# display.net
KiCad netlist of a schematic drawn in EAGLE
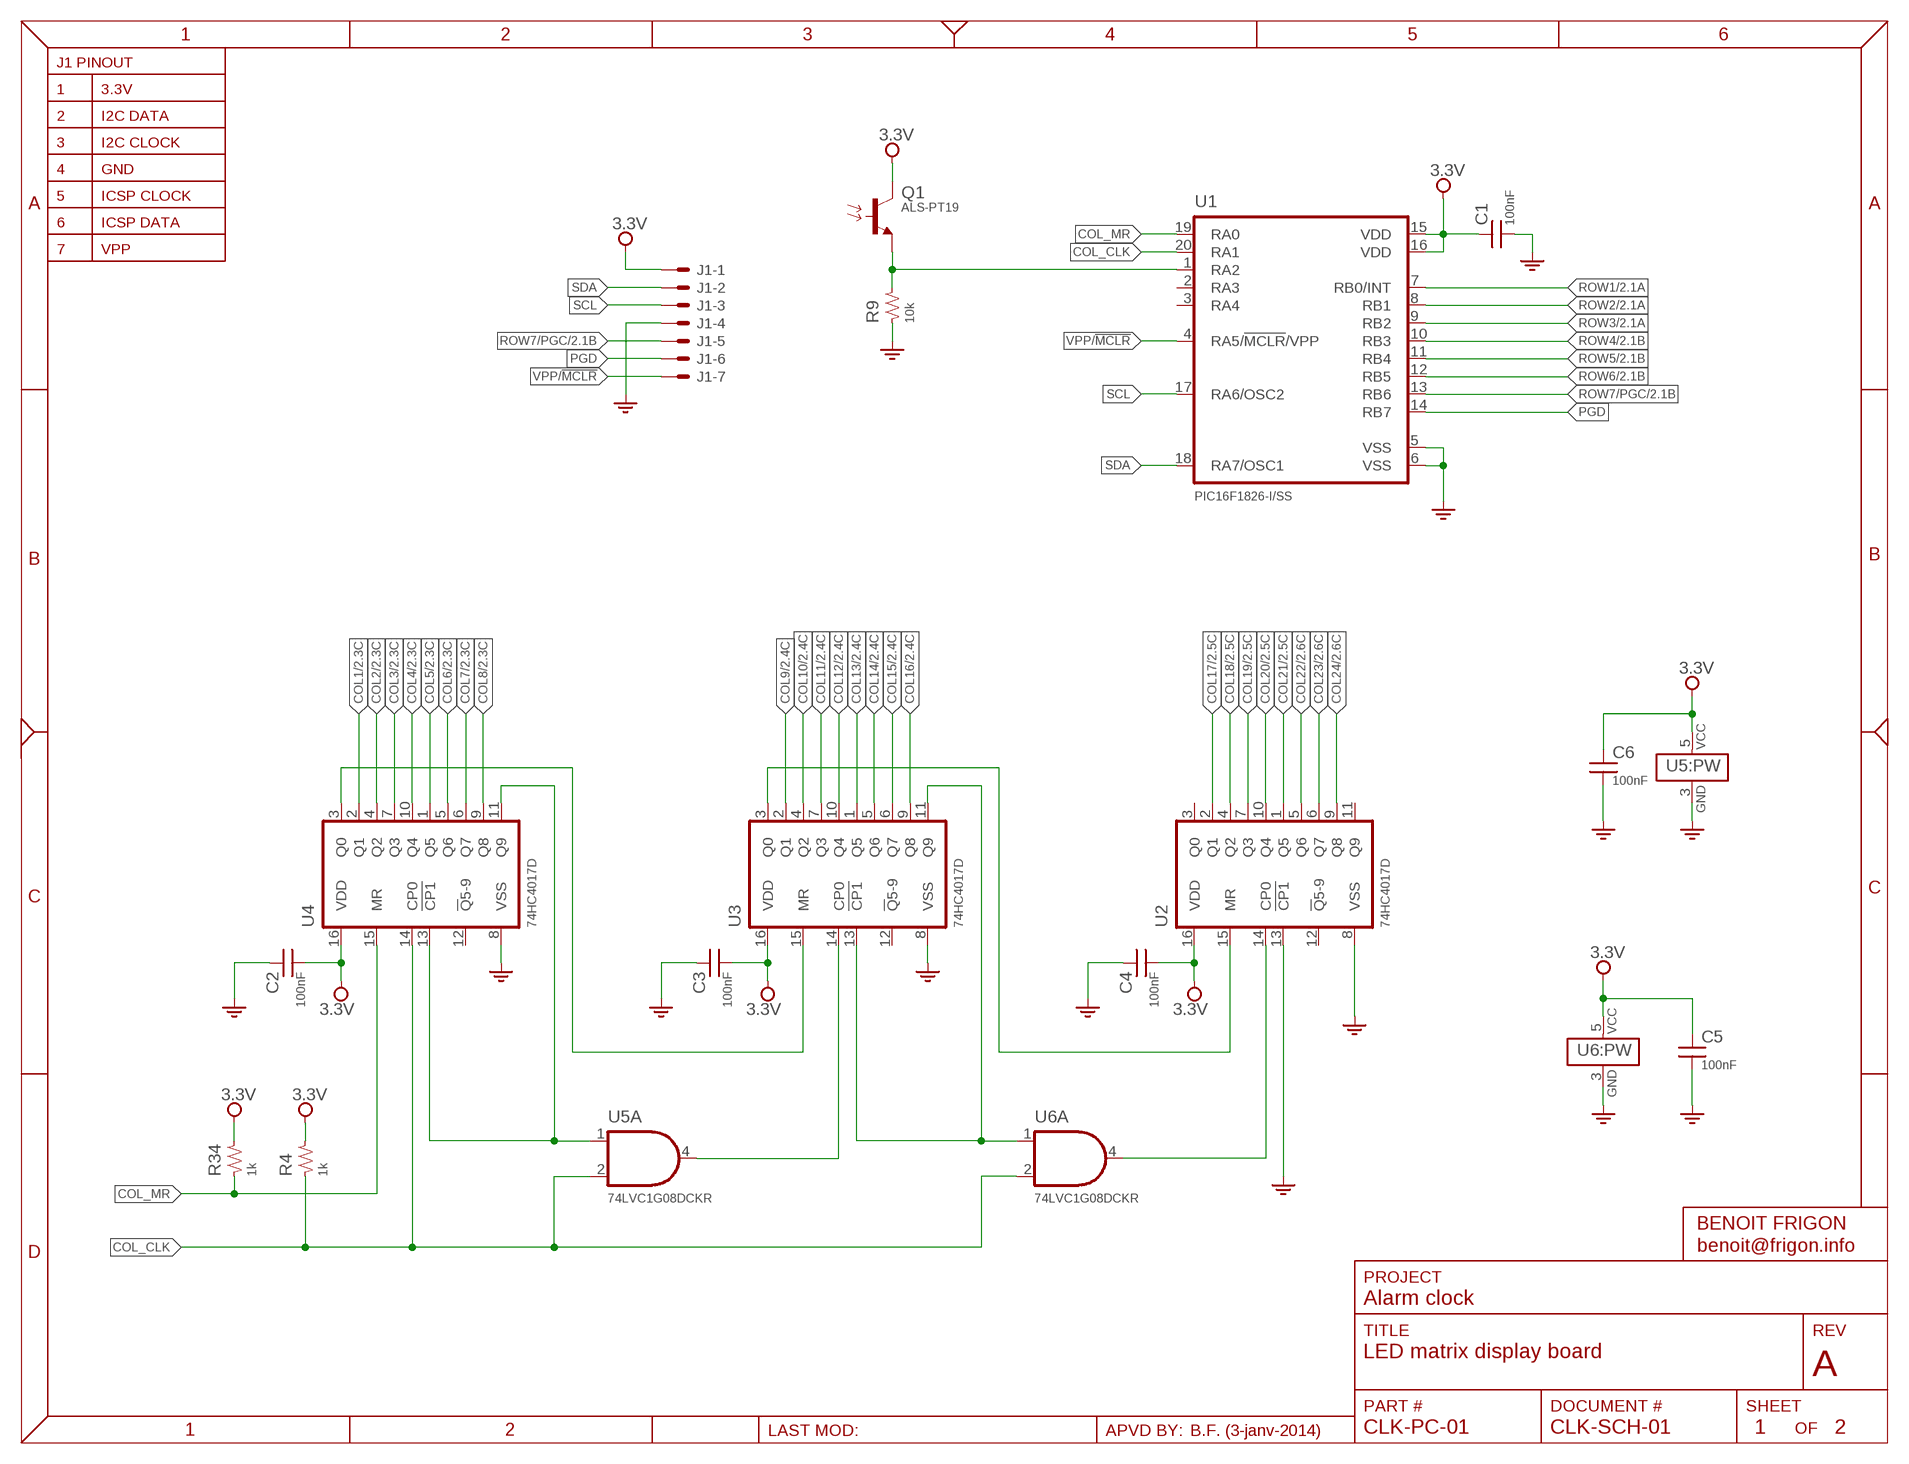
[diagram p0: schematic, sheet 1]
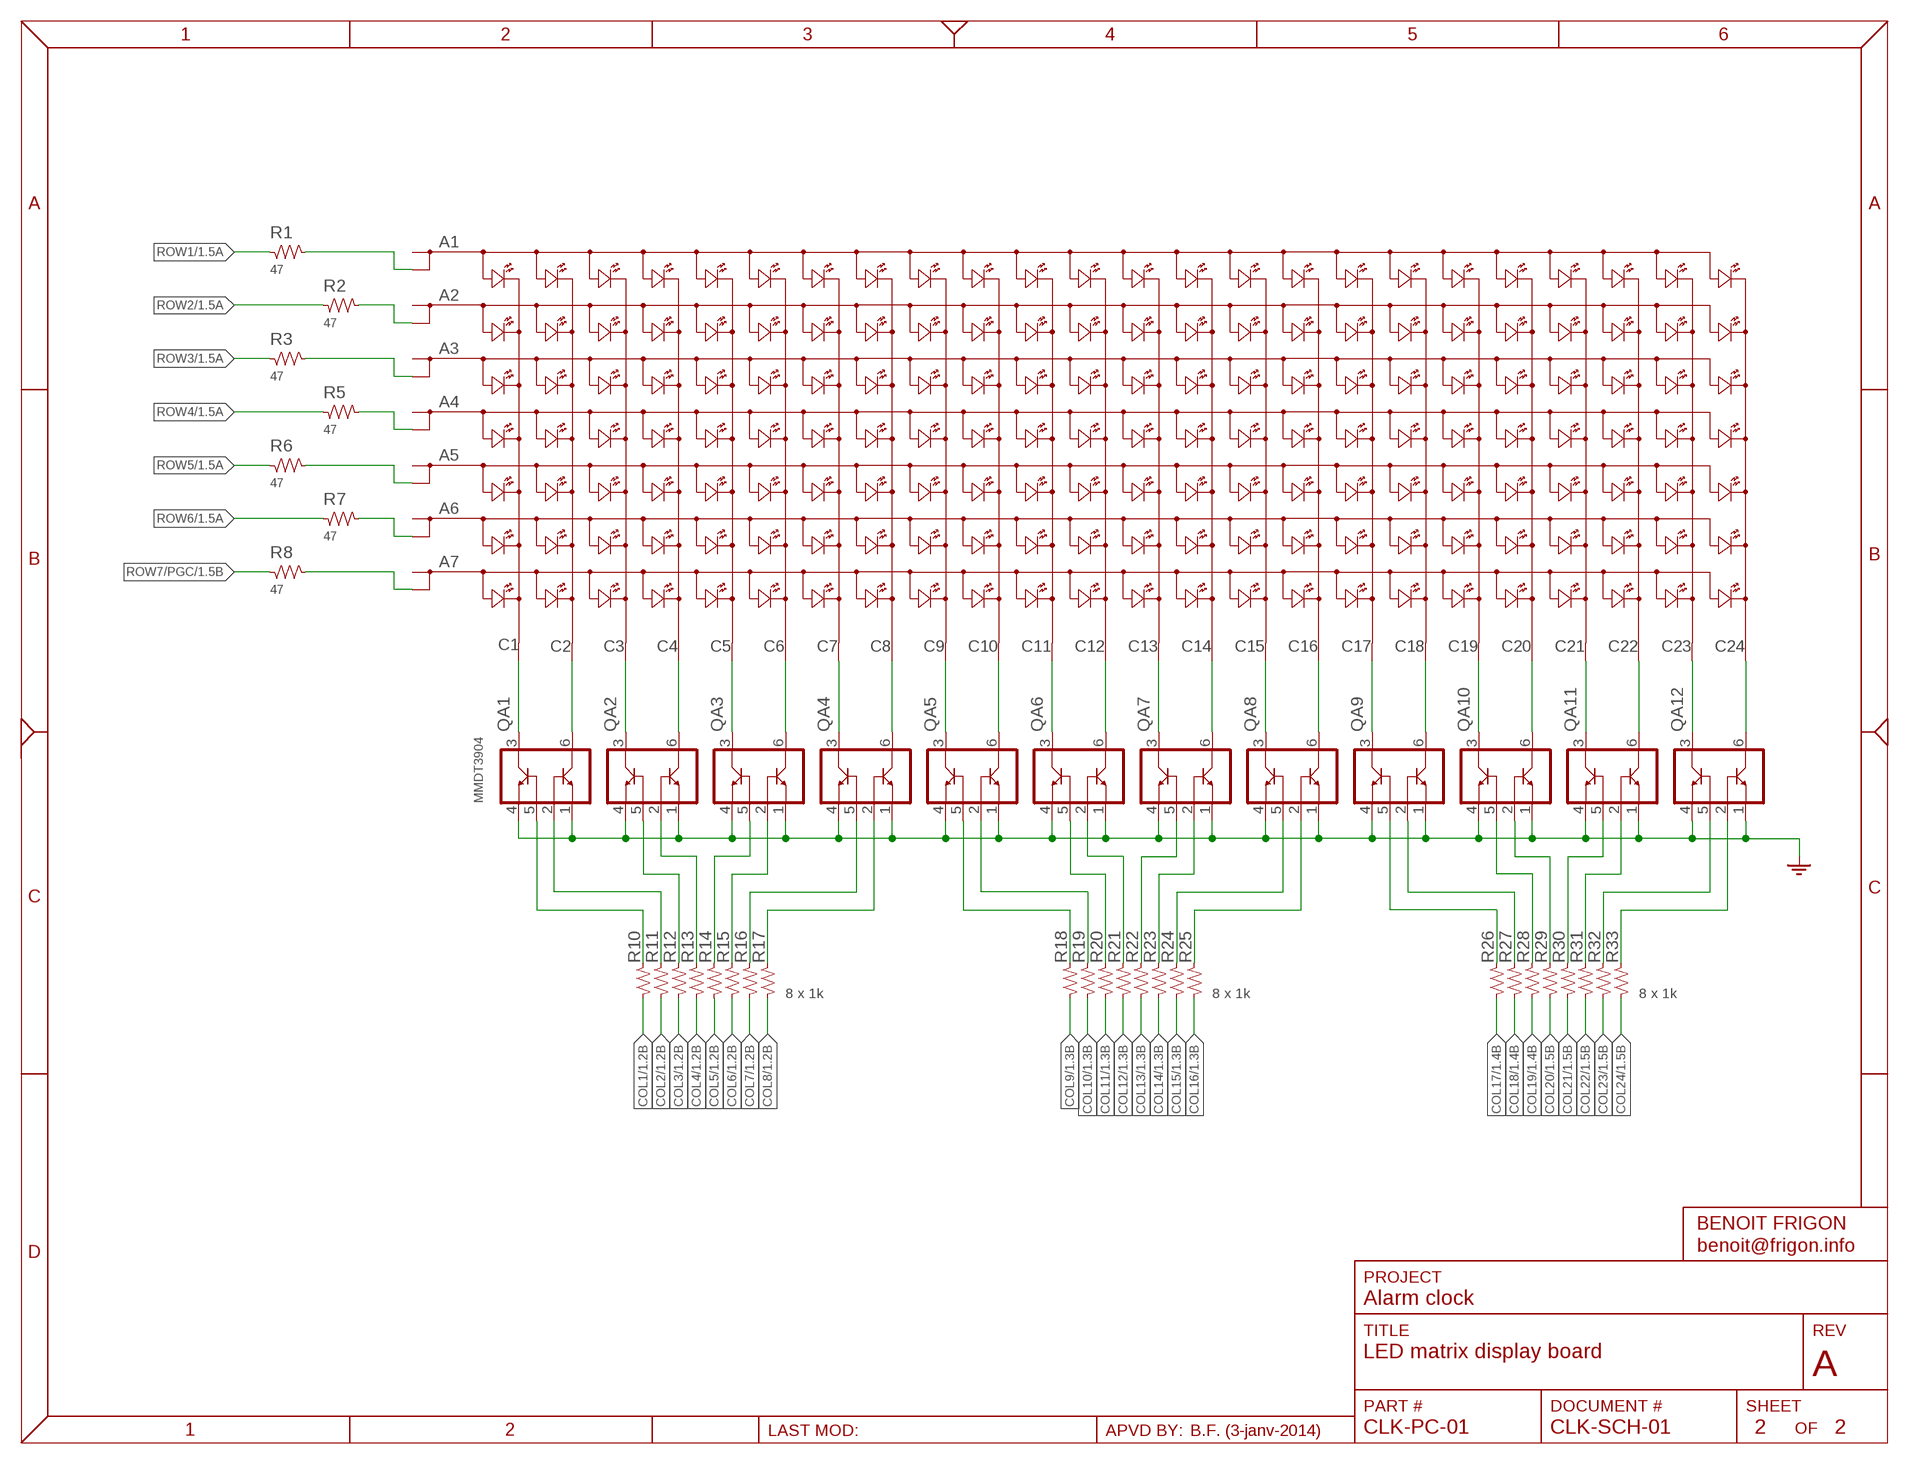
[diagram p1: schematic, sheet 2]

(export (version "E")
  (design (tool "Eeschema 10.0.6"))
  (components
    (comp (ref "QA1")
      (value "MMDT3904")
      (footprint "eagle-import:SOT363")
      (fields (field (name "MFG") "Diodes Inc."))
      (libsource (lib "eagle-import") (part "MMDT3904"))
    )
    (comp (ref "QA2")
      (value "MMDT3904")
      (footprint "eagle-import:SOT363")
      (fields (field (name "MFG") "Diodes Inc."))
      (libsource (lib "eagle-import") (part "MMDT3904"))
    )
    (comp (ref "QA3")
      (value "MMDT3904")
      (footprint "eagle-import:SOT363")
      (fields (field (name "MFG") "Diodes Inc."))
      (libsource (lib "eagle-import") (part "MMDT3904"))
    )
    (comp (ref "QA4")
      (value "MMDT3904")
      (footprint "eagle-import:SOT363")
      (fields (field (name "MFG") "Diodes Inc."))
      (libsource (lib "eagle-import") (part "MMDT3904"))
    )
    (comp (ref "QA5")
      (value "MMDT3904")
      (footprint "eagle-import:SOT363")
      (fields (field (name "MFG") "Diodes Inc."))
      (libsource (lib "eagle-import") (part "MMDT3904"))
    )
    (comp (ref "QA6")
      (value "MMDT3904")
      (footprint "eagle-import:SOT363")
      (fields (field (name "MFG") "Diodes Inc."))
      (libsource (lib "eagle-import") (part "MMDT3904"))
    )
    (comp (ref "QA7")
      (value "MMDT3904")
      (footprint "eagle-import:SOT363")
      (fields (field (name "MFG") "Diodes Inc."))
      (libsource (lib "eagle-import") (part "MMDT3904"))
    )
    (comp (ref "QA8")
      (value "MMDT3904")
      (footprint "eagle-import:SOT363")
      (fields (field (name "MFG") "Diodes Inc."))
      (libsource (lib "eagle-import") (part "MMDT3904"))
    )
    (comp (ref "QA9")
      (value "MMDT3904")
      (footprint "eagle-import:SOT363")
      (fields (field (name "MFG") "Diodes Inc."))
      (libsource (lib "eagle-import") (part "MMDT3904"))
    )
    (comp (ref "QA10")
      (value "MMDT3904")
      (footprint "eagle-import:SOT363")
      (fields (field (name "MFG") "Diodes Inc."))
      (libsource (lib "eagle-import") (part "MMDT3904"))
    )
    (comp (ref "QA11")
      (value "MMDT3904")
      (footprint "eagle-import:SOT363")
      (fields (field (name "MFG") "Diodes Inc."))
      (libsource (lib "eagle-import") (part "MMDT3904"))
    )
    (comp (ref "QA12")
      (value "MMDT3904")
      (footprint "eagle-import:SOT363")
      (fields (field (name "MFG") "Diodes Inc."))
      (libsource (lib "eagle-import") (part "MMDT3904"))
    )
    (comp (ref "R1")
      (value "47")
      (footprint "eagle-import:SMD_0603")
      (description "{DESCRIPTION} - SMT 0603 - {VALUE}")
      (fields (field (name "PACKAGE") "SMT 0603") (field (name "PRICE") "0.00"))
      (libsource (lib "eagle-import") (part "RES-0603"))
    )
    (comp (ref "R2")
      (value "47")
      (footprint "eagle-import:SMD_0603")
      (description "{DESCRIPTION} - SMT 0603 - {VALUE}")
      (fields (field (name "PACKAGE") "SMT 0603") (field (name "PRICE") "0.00"))
      (libsource (lib "eagle-import") (part "RES-0603"))
    )
    (comp (ref "R3")
      (value "47")
      (footprint "eagle-import:SMD_0603")
      (description "{DESCRIPTION} - SMT 0603 - {VALUE}")
      (fields (field (name "PACKAGE") "SMT 0603") (field (name "PRICE") "0.00"))
      (libsource (lib "eagle-import") (part "RES-0603"))
    )
    (comp (ref "R5")
      (value "47")
      (footprint "eagle-import:SMD_0603")
      (description "{DESCRIPTION} - SMT 0603 - {VALUE}")
      (fields (field (name "PACKAGE") "SMT 0603") (field (name "PRICE") "0.00"))
      (libsource (lib "eagle-import") (part "RES-0603"))
    )
    (comp (ref "R6")
      (value "47")
      (footprint "eagle-import:SMD_0603")
      (description "{DESCRIPTION} - SMT 0603 - {VALUE}")
      (fields (field (name "PACKAGE") "SMT 0603") (field (name "PRICE") "0.00"))
      (libsource (lib "eagle-import") (part "RES-0603"))
    )
    (comp (ref "R7")
      (value "47")
      (footprint "eagle-import:SMD_0603")
      (description "{DESCRIPTION} - SMT 0603 - {VALUE}")
      (fields (field (name "PACKAGE") "SMT 0603") (field (name "PRICE") "0.00"))
      (libsource (lib "eagle-import") (part "RES-0603"))
    )
    (comp (ref "R8")
      (value "47")
      (footprint "eagle-import:SMD_0603")
      (description "{DESCRIPTION} - SMT 0603 - {VALUE}")
      (fields (field (name "PACKAGE") "SMT 0603") (field (name "PRICE") "0.00"))
      (libsource (lib "eagle-import") (part "RES-0603"))
    )
    (comp (ref "R10")
      (value "1k")
      (footprint "eagle-import:SMD_0603")
      (fields (field (name "PRICE") "0.00"))
      (libsource (lib "eagle-import") (part "RES-0603"))
    )
    (comp (ref "R11")
      (value "1k")
      (footprint "eagle-import:SMD_0603")
      (description "{DESCRIPTION} - SMT 0603 - {VALUE}")
      (fields (field (name "PACKAGE") "SMT 0603") (field (name "PRICE") "0.00"))
      (libsource (lib "eagle-import") (part "RES-0603"))
    )
    (comp (ref "R12")
      (value "1k")
      (footprint "eagle-import:SMD_0603")
      (description "{DESCRIPTION} - SMT 0603 - {VALUE}")
      (fields (field (name "PACKAGE") "SMT 0603") (field (name "PRICE") "0.00"))
      (libsource (lib "eagle-import") (part "RES-0603"))
    )
    (comp (ref "R13")
      (value "1k")
      (footprint "eagle-import:SMD_0603")
      (description "{DESCRIPTION} - SMT 0603 - {VALUE}")
      (fields (field (name "PACKAGE") "SMT 0603") (field (name "PRICE") "0.00"))
      (libsource (lib "eagle-import") (part "RES-0603"))
    )
    (comp (ref "R14")
      (value "1k")
      (footprint "eagle-import:SMD_0603")
      (description "{DESCRIPTION} - SMT 0603 - {VALUE}")
      (fields (field (name "PACKAGE") "SMT 0603") (field (name "PRICE") "0.00"))
      (libsource (lib "eagle-import") (part "RES-0603"))
    )
    (comp (ref "R15")
      (value "1k")
      (footprint "eagle-import:SMD_0603")
      (description "{DESCRIPTION} - SMT 0603 - {VALUE}")
      (fields (field (name "PACKAGE") "SMT 0603") (field (name "PRICE") "0.00"))
      (libsource (lib "eagle-import") (part "RES-0603"))
    )
    (comp (ref "R16")
      (value "1k")
      (footprint "eagle-import:SMD_0603")
      (description "{DESCRIPTION} - SMT 0603 - {VALUE}")
      (fields (field (name "PACKAGE") "SMT 0603") (field (name "PRICE") "0.00"))
      (libsource (lib "eagle-import") (part "RES-0603"))
    )
    (comp (ref "R17")
      (value "1k")
      (footprint "eagle-import:SMD_0603")
      (description "{DESCRIPTION} - SMT 0603 - {VALUE}")
      (fields (field (name "PACKAGE") "SMT 0603") (field (name "PRICE") "0.00"))
      (libsource (lib "eagle-import") (part "RES-0603"))
    )
    (comp (ref "R18")
      (value "1k")
      (footprint "eagle-import:SMD_0603")
      (description "{DESCRIPTION} - SMT 0603 - {VALUE}")
      (fields (field (name "PACKAGE") "SMT 0603") (field (name "PRICE") "0.00"))
      (libsource (lib "eagle-import") (part "RES-0603"))
    )
    (comp (ref "R19")
      (value "1k")
      (footprint "eagle-import:SMD_0603")
      (description "{DESCRIPTION} - SMT 0603 - {VALUE}")
      (fields (field (name "PACKAGE") "SMT 0603") (field (name "PRICE") "0.00"))
      (libsource (lib "eagle-import") (part "RES-0603"))
    )
    (comp (ref "R20")
      (value "1k")
      (footprint "eagle-import:SMD_0603")
      (description "{DESCRIPTION} - SMT 0603 - {VALUE}")
      (fields (field (name "PACKAGE") "SMT 0603") (field (name "PRICE") "0.00"))
      (libsource (lib "eagle-import") (part "RES-0603"))
    )
    (comp (ref "R21")
      (value "1k")
      (footprint "eagle-import:SMD_0603")
      (description "{DESCRIPTION} - SMT 0603 - {VALUE}")
      (fields (field (name "PACKAGE") "SMT 0603") (field (name "PRICE") "0.00"))
      (libsource (lib "eagle-import") (part "RES-0603"))
    )
    (comp (ref "R22")
      (value "1k")
      (footprint "eagle-import:SMD_0603")
      (description "{DESCRIPTION} - SMT 0603 - {VALUE}")
      (fields (field (name "PACKAGE") "SMT 0603") (field (name "PRICE") "0.00"))
      (libsource (lib "eagle-import") (part "RES-0603"))
    )
    (comp (ref "R23")
      (value "1k")
      (footprint "eagle-import:SMD_0603")
      (description "{DESCRIPTION} - SMT 0603 - {VALUE}")
      (fields (field (name "PACKAGE") "SMT 0603") (field (name "PRICE") "0.00"))
      (libsource (lib "eagle-import") (part "RES-0603"))
    )
    (comp (ref "R24")
      (value "1k")
      (footprint "eagle-import:SMD_0603")
      (description "{DESCRIPTION} - SMT 0603 - {VALUE}")
      (fields (field (name "PACKAGE") "SMT 0603") (field (name "PRICE") "0.00"))
      (libsource (lib "eagle-import") (part "RES-0603"))
    )
    (comp (ref "R25")
      (value "1k")
      (footprint "eagle-import:SMD_0603")
      (description "{DESCRIPTION} - SMT 0603 - {VALUE}")
      (fields (field (name "PACKAGE") "SMT 0603") (field (name "PRICE") "0.00"))
      (libsource (lib "eagle-import") (part "RES-0603"))
    )
    (comp (ref "R26")
      (value "1k")
      (footprint "eagle-import:SMD_0603")
      (description "{DESCRIPTION} - SMT 0603 - {VALUE}")
      (fields (field (name "PACKAGE") "SMT 0603") (field (name "PRICE") "0.00"))
      (libsource (lib "eagle-import") (part "RES-0603"))
    )
    (comp (ref "R27")
      (value "1k")
      (footprint "eagle-import:SMD_0603")
      (description "{DESCRIPTION} - SMT 0603 - {VALUE}")
      (fields (field (name "PACKAGE") "SMT 0603") (field (name "PRICE") "0.00"))
      (libsource (lib "eagle-import") (part "RES-0603"))
    )
    (comp (ref "R28")
      (value "1k")
      (footprint "eagle-import:SMD_0603")
      (description "{DESCRIPTION} - SMT 0603 - {VALUE}")
      (fields (field (name "PACKAGE") "SMT 0603") (field (name "PRICE") "0.00"))
      (libsource (lib "eagle-import") (part "RES-0603"))
    )
    (comp (ref "R29")
      (value "1k")
      (footprint "eagle-import:SMD_0603")
      (description "{DESCRIPTION} - SMT 0603 - {VALUE}")
      (fields (field (name "PACKAGE") "SMT 0603") (field (name "PRICE") "0.00"))
      (libsource (lib "eagle-import") (part "RES-0603"))
    )
    (comp (ref "R30")
      (value "1k")
      (footprint "eagle-import:SMD_0603")
      (description "{DESCRIPTION} - SMT 0603 - {VALUE}")
      (fields (field (name "PACKAGE") "SMT 0603") (field (name "PRICE") "0.00"))
      (libsource (lib "eagle-import") (part "RES-0603"))
    )
    (comp (ref "R31")
      (value "1k")
      (footprint "eagle-import:SMD_0603")
      (description "{DESCRIPTION} - SMT 0603 - {VALUE}")
      (fields (field (name "PACKAGE") "SMT 0603") (field (name "PRICE") "0.00"))
      (libsource (lib "eagle-import") (part "RES-0603"))
    )
    (comp (ref "R32")
      (value "1k")
      (footprint "eagle-import:SMD_0603")
      (description "{DESCRIPTION} - SMT 0603 - {VALUE}")
      (fields (field (name "PACKAGE") "SMT 0603") (field (name "PRICE") "0.00"))
      (libsource (lib "eagle-import") (part "RES-0603"))
    )
    (comp (ref "R33")
      (value "1k")
      (footprint "eagle-import:SMD_0603")
      (description "{DESCRIPTION} - SMT 0603 - {VALUE}")
      (fields (field (name "PACKAGE") "SMT 0603") (field (name "PRICE") "0.00"))
      (libsource (lib "eagle-import") (part "RES-0603"))
    )
    (comp (ref "U$1")
      (value "LED_MATRIX_V_24X7")
      (footprint "eagle-import:LED_MATRIX_V_24X7")
      (libsource (lib "eagle-import") (part "LED_MATRIX_V_24X7"))
    )
    (comp (ref "C1")
      (value "100nF")
      (footprint "eagle-import:SMD_0603")
      (fields (field (name "PRICE") "0.00"))
      (libsource (lib "eagle-import") (part "CAP-0603"))
    )
    (comp (ref "C2")
      (value "100nF")
      (footprint "eagle-import:SMD_0603")
      (fields (field (name "PRICE") "0.00"))
      (libsource (lib "eagle-import") (part "CAP-0603"))
    )
    (comp (ref "C3")
      (value "100nF")
      (footprint "eagle-import:SMD_0603")
      (description "{DESCRIPTION} - SMT 0603 - {value}")
      (fields (field (name "PACKAGE") "SMT 0603") (field (name "PRICE") "0.00"))
      (libsource (lib "eagle-import") (part "CAP-0603"))
    )
    (comp (ref "C4")
      (value "100nF")
      (footprint "eagle-import:SMD_0603")
      (description "{DESCRIPTION} - SMT 0603 - {value}")
      (fields (field (name "PACKAGE") "SMT 0603") (field (name "PRICE") "0.00"))
      (libsource (lib "eagle-import") (part "CAP-0603"))
    )
    (comp (ref "C5")
      (value "100nF")
      (footprint "eagle-import:SMD_0603")
      (libsource (lib "eagle-import") (part "CAP-0603"))
    )
    (comp (ref "C6")
      (value "100nF")
      (footprint "eagle-import:SMD_0603")
      (libsource (lib "eagle-import") (part "CAP-0603"))
    )
    (comp (ref "J1")
      (value "SNG-2MM-HEADER-07-V")
      (footprint "eagle-import:DF3X-7P-2DSA")
      (fields
        (field (name "MFG") "Hirose Electronic")
        (field (name "PART_NO") "DF3A-7P-2DSA")
        (field (name "SKU") "H2099-ND")
        (field (name "PRICE") "0.37")
        (field (name "SUPPLIER") "Digi-Key")
      )
      (libsource (lib "eagle-import") (part "SNG-2MM-HEADER-07-V"))
    )
    (comp (ref "Q1")
      (value "ALS-PT19")
      (footprint "eagle-import:ALS-PT19")
      (fields
        (field (name "MFG") "Everlight")
        (field (name "PART_NO") "ALS-PT19-315C/L177/TR8")
        (field (name "PART_NO_1") "ALS-PT19-315C/L177/TR8")
      )
      (libsource (lib "eagle-import") (part "ALS-PT19"))
    )
    (comp (ref "R4")
      (value "1k")
      (footprint "eagle-import:SMD_0603")
      (fields (field (name "PRICE") "0.00"))
      (libsource (lib "eagle-import") (part "RES-0603"))
    )
    (comp (ref "R9")
      (value "10k")
      (footprint "eagle-import:SMD_0603")
      (libsource (lib "eagle-import") (part "RES-0603"))
    )
    (comp (ref "R34")
      (value "1k")
      (footprint "eagle-import:SMD_0603")
      (fields (field (name "PRICE") "0.00"))
      (libsource (lib "eagle-import") (part "RES-0603"))
    )
    (comp (ref "U1")
      (value "PIC16F1826-I/SS")
      (footprint "eagle-import:SSOP20")
      (fields (field (name "MFG") "Microchip"))
      (libsource (lib "eagle-import") (part "PIC16F1826-?I/SS"))
    )
    (comp (ref "U2")
      (value "74HC4017D")
      (footprint "eagle-import:SOIC16N")
      (fields (field (name "MFG") "NXP Semiconductors") (field (name "PART_NO") "74HC4017D,653"))
      (libsource (lib "eagle-import") (part "74HC4017D"))
    )
    (comp (ref "U3")
      (value "74HC4017D")
      (footprint "eagle-import:SOIC16N")
      (fields (field (name "MFG") "NXP Semiconductors") (field (name "PART_NO") "74HC4017D,653"))
      (libsource (lib "eagle-import") (part "74HC4017D"))
    )
    (comp (ref "U4")
      (value "74HC4017D")
      (footprint "eagle-import:SOIC16N")
      (fields (field (name "MFG") "NXP Semiconductors") (field (name "PART_NO") "74HC4017D,653"))
      (libsource (lib "eagle-import") (part "74HC4017D"))
    )
    (comp (ref "U5")
      (value "74LVC1G08DCKR")
      (footprint "eagle-import:SC70-5")
      (fields
        (field (name "MFG") "Texas Instruments")
        (field (name "MFG_1") "Texas Instruments")
        (field (name "PRICE") "0.29")
        (field (name "SKU") "296-11602-1-ND")
        (field (name "SUPPLIER") "Digi-Key")
      )
      (libsource (lib "eagle-import") (part "741G08DCKRLVC"))
    )
    (comp (ref "U6")
      (value "74LVC1G08DCKR")
      (footprint "eagle-import:SC70-5")
      (fields
        (field (name "MFG") "Texas Instruments")
        (field (name "MFG_1") "Texas Instruments")
        (field (name "PRICE") "0.29")
        (field (name "SKU") "296-11602-1-ND")
        (field (name "SUPPLIER") "Digi-Key")
      )
      (libsource (lib "eagle-import") (part "741G08DCKRLVC"))
    )
  )
  (nets
    (net (code "1") (name "3.3V") (class "Default")
      (node (ref "C1") (pin "1") (pinfunction "1_1") (pintype "passive"))
      (node (ref "C2") (pin "2") (pinfunction "2_2") (pintype "passive"))
      (node (ref "C3") (pin "2") (pinfunction "2_2") (pintype "passive"))
      (node (ref "C4") (pin "2") (pinfunction "2_2") (pintype "passive"))
      (node (ref "C5") (pin "1") (pinfunction "1_1") (pintype "passive"))
      (node (ref "C6") (pin "1") (pinfunction "1_1") (pintype "passive"))
      (node (ref "J1") (pin "1") (pinfunction "S_1") (pintype "bidirectional"))
      (node (ref "Q1") (pin "C") (pinfunction "C_C") (pintype "passive"))
      (node (ref "R34") (pin "2") (pinfunction "2_2") (pintype "passive"))
      (node (ref "R4") (pin "2") (pinfunction "2_2") (pintype "passive"))
      (node (ref "U1") (pin "15") (pinfunction "VDD_15") (pintype "power_in"))
      (node (ref "U1") (pin "16") (pinfunction "VDD_16") (pintype "power_in"))
      (node (ref "U2") (pin "16") (pinfunction "VDD_16") (pintype "bidirectional"))
      (node (ref "U3") (pin "16") (pinfunction "VDD_16") (pintype "bidirectional"))
      (node (ref "U4") (pin "16") (pinfunction "VDD_16") (pintype "bidirectional"))
      (node (ref "U5") (pin "5") (pinfunction "VCC_5") (pintype "power_in"))
      (node (ref "U6") (pin "5") (pinfunction "VCC_5") (pintype "power_in"))
    )
    (net (code "2") (name "COL1") (class "Default")
      (node (ref "R10") (pin "1") (pinfunction "1_1") (pintype "passive"))
      (node (ref "U4") (pin "2") (pinfunction "Q1_2") (pintype "bidirectional"))
    )
    (net (code "3") (name "COL2") (class "Default")
      (node (ref "R11") (pin "1") (pinfunction "1_1") (pintype "passive"))
      (node (ref "U4") (pin "4") (pinfunction "Q2_4") (pintype "bidirectional"))
    )
    (net (code "4") (name "COL3") (class "Default")
      (node (ref "R12") (pin "1") (pinfunction "1_1") (pintype "passive"))
      (node (ref "U4") (pin "7") (pinfunction "Q3_7") (pintype "bidirectional"))
    )
    (net (code "5") (name "COL4") (class "Default")
      (node (ref "R13") (pin "1") (pinfunction "1_1") (pintype "passive"))
      (node (ref "U4") (pin "10") (pinfunction "Q4_10") (pintype "bidirectional"))
    )
    (net (code "6") (name "COL5") (class "Default")
      (node (ref "R14") (pin "1") (pinfunction "1_1") (pintype "passive"))
      (node (ref "U4") (pin "1") (pinfunction "Q5_1") (pintype "bidirectional"))
    )
    (net (code "7") (name "COL6") (class "Default")
      (node (ref "R15") (pin "1") (pinfunction "1_1") (pintype "passive"))
      (node (ref "U4") (pin "5") (pinfunction "Q6_5") (pintype "bidirectional"))
    )
    (net (code "8") (name "COL7") (class "Default")
      (node (ref "R16") (pin "1") (pinfunction "1_1") (pintype "passive"))
      (node (ref "U4") (pin "6") (pinfunction "Q7_6") (pintype "bidirectional"))
    )
    (net (code "9") (name "COL8") (class "Default")
      (node (ref "R17") (pin "1") (pinfunction "1_1") (pintype "passive"))
      (node (ref "U4") (pin "9") (pinfunction "Q8_9") (pintype "bidirectional"))
    )
    (net (code "10") (name "COL9") (class "Default")
      (node (ref "R18") (pin "1") (pinfunction "1_1") (pintype "passive"))
      (node (ref "U3") (pin "2") (pinfunction "Q1_2") (pintype "bidirectional"))
    )
    (net (code "11") (name "COL10") (class "Default")
      (node (ref "R19") (pin "1") (pinfunction "1_1") (pintype "passive"))
      (node (ref "U3") (pin "4") (pinfunction "Q2_4") (pintype "bidirectional"))
    )
    (net (code "12") (name "COL11") (class "Default")
      (node (ref "R20") (pin "1") (pinfunction "1_1") (pintype "passive"))
      (node (ref "U3") (pin "7") (pinfunction "Q3_7") (pintype "bidirectional"))
    )
    (net (code "13") (name "COL12") (class "Default")
      (node (ref "R21") (pin "1") (pinfunction "1_1") (pintype "passive"))
      (node (ref "U3") (pin "10") (pinfunction "Q4_10") (pintype "bidirectional"))
    )
    (net (code "14") (name "COL13") (class "Default")
      (node (ref "R22") (pin "1") (pinfunction "1_1") (pintype "passive"))
      (node (ref "U3") (pin "1") (pinfunction "Q5_1") (pintype "bidirectional"))
    )
    (net (code "15") (name "COL14") (class "Default")
      (node (ref "R23") (pin "1") (pinfunction "1_1") (pintype "passive"))
      (node (ref "U3") (pin "5") (pinfunction "Q6_5") (pintype "bidirectional"))
    )
    (net (code "16") (name "COL15") (class "Default")
      (node (ref "R24") (pin "1") (pinfunction "1_1") (pintype "passive"))
      (node (ref "U3") (pin "6") (pinfunction "Q7_6") (pintype "bidirectional"))
    )
    (net (code "17") (name "COL16") (class "Default")
      (node (ref "R25") (pin "1") (pinfunction "1_1") (pintype "passive"))
      (node (ref "U3") (pin "9") (pinfunction "Q8_9") (pintype "bidirectional"))
    )
    (net (code "18") (name "COL17") (class "Default")
      (node (ref "R26") (pin "1") (pinfunction "1_1") (pintype "passive"))
      (node (ref "U2") (pin "2") (pinfunction "Q1_2") (pintype "bidirectional"))
    )
    (net (code "19") (name "COL18") (class "Default")
      (node (ref "R27") (pin "1") (pinfunction "1_1") (pintype "passive"))
      (node (ref "U2") (pin "4") (pinfunction "Q2_4") (pintype "bidirectional"))
    )
    (net (code "20") (name "COL19") (class "Default")
      (node (ref "R28") (pin "1") (pinfunction "1_1") (pintype "passive"))
      (node (ref "U2") (pin "7") (pinfunction "Q3_7") (pintype "bidirectional"))
    )
    (net (code "21") (name "COL20") (class "Default")
      (node (ref "R29") (pin "1") (pinfunction "1_1") (pintype "passive"))
      (node (ref "U2") (pin "10") (pinfunction "Q4_10") (pintype "bidirectional"))
    )
    (net (code "22") (name "COL21") (class "Default")
      (node (ref "R30") (pin "1") (pinfunction "1_1") (pintype "passive"))
      (node (ref "U2") (pin "1") (pinfunction "Q5_1") (pintype "bidirectional"))
    )
    (net (code "23") (name "COL22") (class "Default")
      (node (ref "R31") (pin "1") (pinfunction "1_1") (pintype "passive"))
      (node (ref "U2") (pin "5") (pinfunction "Q6_5") (pintype "bidirectional"))
    )
    (net (code "24") (name "COL23") (class "Default")
      (node (ref "R32") (pin "1") (pinfunction "1_1") (pintype "passive"))
      (node (ref "U2") (pin "6") (pinfunction "Q7_6") (pintype "bidirectional"))
    )
    (net (code "25") (name "COL24") (class "Default")
      (node (ref "R33") (pin "1") (pinfunction "1_1") (pintype "passive"))
      (node (ref "U2") (pin "9") (pinfunction "Q8_9") (pintype "bidirectional"))
    )
    (net (code "26") (name "COL_CLK") (class "Default")
      (node (ref "R4") (pin "1") (pinfunction "1_1") (pintype "passive"))
      (node (ref "U1") (pin "20") (pinfunction "RA1_20") (pintype "bidirectional"))
      (node (ref "U4") (pin "14") (pinfunction "CP0_14") (pintype "bidirectional"))
      (node (ref "U5") (pin "2") (pinfunction "I1_2") (pintype "input"))
      (node (ref "U6") (pin "2") (pinfunction "I1_2") (pintype "input"))
    )
    (net (code "27") (name "COL_MR") (class "Default")
      (node (ref "R34") (pin "1") (pinfunction "1_1") (pintype "passive"))
      (node (ref "U1") (pin "19") (pinfunction "RA0_19") (pintype "bidirectional"))
      (node (ref "U4") (pin "15") (pinfunction "MR_15") (pintype "bidirectional"))
    )
    (net (code "28") (name "GND") (class "Default")
      (node (ref "C1") (pin "2") (pinfunction "2_2") (pintype "passive"))
      (node (ref "C2") (pin "1") (pinfunction "1_1") (pintype "passive"))
      (node (ref "C3") (pin "1") (pinfunction "1_1") (pintype "passive"))
      (node (ref "C4") (pin "1") (pinfunction "1_1") (pintype "passive"))
      (node (ref "C5") (pin "2") (pinfunction "2_2") (pintype "passive"))
      (node (ref "C6") (pin "2") (pinfunction "2_2") (pintype "passive"))
      (node (ref "J1") (pin "4") (pinfunction "S_4") (pintype "bidirectional"))
      (node (ref "QA1") (pin "1") (pinfunction "E2_1") (pintype "bidirectional"))
      (node (ref "QA1") (pin "4") (pinfunction "E1_4") (pintype "bidirectional"))
      (node (ref "QA10") (pin "1") (pinfunction "E2_1") (pintype "bidirectional"))
      (node (ref "QA10") (pin "4") (pinfunction "E1_4") (pintype "bidirectional"))
      (node (ref "QA11") (pin "1") (pinfunction "E2_1") (pintype "bidirectional"))
      (node (ref "QA11") (pin "4") (pinfunction "E1_4") (pintype "bidirectional"))
      (node (ref "QA12") (pin "1") (pinfunction "E2_1") (pintype "bidirectional"))
      (node (ref "QA12") (pin "4") (pinfunction "E1_4") (pintype "bidirectional"))
      (node (ref "QA2") (pin "1") (pinfunction "E2_1") (pintype "bidirectional"))
      (node (ref "QA2") (pin "4") (pinfunction "E1_4") (pintype "bidirectional"))
      (node (ref "QA3") (pin "1") (pinfunction "E2_1") (pintype "bidirectional"))
      (node (ref "QA3") (pin "4") (pinfunction "E1_4") (pintype "bidirectional"))
      (node (ref "QA4") (pin "1") (pinfunction "E2_1") (pintype "bidirectional"))
      (node (ref "QA4") (pin "4") (pinfunction "E1_4") (pintype "bidirectional"))
      (node (ref "QA5") (pin "1") (pinfunction "E2_1") (pintype "bidirectional"))
      (node (ref "QA5") (pin "4") (pinfunction "E1_4") (pintype "bidirectional"))
      (node (ref "QA6") (pin "1") (pinfunction "E2_1") (pintype "bidirectional"))
      (node (ref "QA6") (pin "4") (pinfunction "E1_4") (pintype "bidirectional"))
      (node (ref "QA7") (pin "1") (pinfunction "E2_1") (pintype "bidirectional"))
      (node (ref "QA7") (pin "4") (pinfunction "E1_4") (pintype "bidirectional"))
      (node (ref "QA8") (pin "1") (pinfunction "E2_1") (pintype "bidirectional"))
      (node (ref "QA8") (pin "4") (pinfunction "E1_4") (pintype "bidirectional"))
      (node (ref "QA9") (pin "1") (pinfunction "E2_1") (pintype "bidirectional"))
      (node (ref "QA9") (pin "4") (pinfunction "E1_4") (pintype "bidirectional"))
      (node (ref "R9") (pin "1") (pinfunction "1_1") (pintype "passive"))
      (node (ref "U1") (pin "5") (pinfunction "VSS_5") (pintype "power_in"))
      (node (ref "U1") (pin "6") (pinfunction "VSS_6") (pintype "power_in"))
      (node (ref "U2") (pin "13") (pinfunction "~{CP1}_13") (pintype "bidirectional"))
      (node (ref "U2") (pin "8") (pinfunction "VSS_8") (pintype "bidirectional"))
      (node (ref "U3") (pin "8") (pinfunction "VSS_8") (pintype "bidirectional"))
      (node (ref "U4") (pin "8") (pinfunction "VSS_8") (pintype "bidirectional"))
      (node (ref "U5") (pin "3") (pinfunction "GND_3") (pintype "power_in"))
      (node (ref "U6") (pin "3") (pinfunction "GND_3") (pintype "power_in"))
    )
    (net (code "29") (name "Net-(QA1-B1)") (class "Default")
      (node (ref "QA1") (pin "5") (pinfunction "B1_5") (pintype "bidirectional"))
      (node (ref "R10") (pin "2") (pinfunction "2_2") (pintype "passive"))
    )
    (net (code "30") (name "Net-(QA1-B2)") (class "Default")
      (node (ref "QA1") (pin "2") (pinfunction "B2_2") (pintype "bidirectional"))
      (node (ref "R11") (pin "2") (pinfunction "2_2") (pintype "passive"))
    )
    (net (code "31") (name "Net-(QA1-C1)") (class "Default")
      (node (ref "QA1") (pin "3") (pinfunction "C1_3") (pintype "bidirectional"))
      (node (ref "U$1") (pin "C1") (pinfunction "C1_C1") (pintype "bidirectional"))
    )
    (net (code "32") (name "Net-(QA1-C2)") (class "Default")
      (node (ref "QA1") (pin "6") (pinfunction "C2_6") (pintype "bidirectional"))
      (node (ref "U$1") (pin "C2") (pinfunction "C2_C2") (pintype "bidirectional"))
    )
    (net (code "33") (name "Net-(QA2-B1)") (class "Default")
      (node (ref "QA2") (pin "5") (pinfunction "B1_5") (pintype "bidirectional"))
      (node (ref "R12") (pin "2") (pinfunction "2_2") (pintype "passive"))
    )
    (net (code "34") (name "Net-(QA2-B2)") (class "Default")
      (node (ref "QA2") (pin "2") (pinfunction "B2_2") (pintype "bidirectional"))
      (node (ref "R13") (pin "2") (pinfunction "2_2") (pintype "passive"))
    )
    (net (code "35") (name "Net-(QA2-C1)") (class "Default")
      (node (ref "QA2") (pin "3") (pinfunction "C1_3") (pintype "bidirectional"))
      (node (ref "U$1") (pin "C3") (pinfunction "C3_C3") (pintype "bidirectional"))
    )
    (net (code "36") (name "Net-(QA2-C2)") (class "Default")
      (node (ref "QA2") (pin "6") (pinfunction "C2_6") (pintype "bidirectional"))
      (node (ref "U$1") (pin "C4") (pinfunction "C4_C4") (pintype "bidirectional"))
    )
    (net (code "37") (name "Net-(QA3-B1)") (class "Default")
      (node (ref "QA3") (pin "5") (pinfunction "B1_5") (pintype "bidirectional"))
      (node (ref "R14") (pin "2") (pinfunction "2_2") (pintype "passive"))
    )
    (net (code "38") (name "Net-(QA3-B2)") (class "Default")
      (node (ref "QA3") (pin "2") (pinfunction "B2_2") (pintype "bidirectional"))
      (node (ref "R15") (pin "2") (pinfunction "2_2") (pintype "passive"))
    )
    (net (code "39") (name "Net-(QA3-C1)") (class "Default")
      (node (ref "QA3") (pin "3") (pinfunction "C1_3") (pintype "bidirectional"))
      (node (ref "U$1") (pin "C5") (pinfunction "C5_C5") (pintype "bidirectional"))
    )
    (net (code "40") (name "Net-(QA3-C2)") (class "Default")
      (node (ref "QA3") (pin "6") (pinfunction "C2_6") (pintype "bidirectional"))
      (node (ref "U$1") (pin "C6") (pinfunction "C6_C6") (pintype "bidirectional"))
    )
    (net (code "41") (name "Net-(QA4-B1)") (class "Default")
      (node (ref "QA4") (pin "5") (pinfunction "B1_5") (pintype "bidirectional"))
      (node (ref "R16") (pin "2") (pinfunction "2_2") (pintype "passive"))
    )
    (net (code "42") (name "Net-(QA4-B2)") (class "Default")
      (node (ref "QA4") (pin "2") (pinfunction "B2_2") (pintype "bidirectional"))
      (node (ref "R17") (pin "2") (pinfunction "2_2") (pintype "passive"))
    )
    (net (code "43") (name "Net-(QA4-C1)") (class "Default")
      (node (ref "QA4") (pin "3") (pinfunction "C1_3") (pintype "bidirectional"))
      (node (ref "U$1") (pin "C7") (pinfunction "C7_C7") (pintype "bidirectional"))
    )
    (net (code "44") (name "Net-(QA4-C2)") (class "Default")
      (node (ref "QA4") (pin "6") (pinfunction "C2_6") (pintype "bidirectional"))
      (node (ref "U$1") (pin "C8") (pinfunction "C8_C8") (pintype "bidirectional"))
    )
    (net (code "45") (name "Net-(QA5-B1)") (class "Default")
      (node (ref "QA5") (pin "5") (pinfunction "B1_5") (pintype "bidirectional"))
      (node (ref "R18") (pin "2") (pinfunction "2_2") (pintype "passive"))
    )
    (net (code "46") (name "Net-(QA5-B2)") (class "Default")
      (node (ref "QA5") (pin "2") (pinfunction "B2_2") (pintype "bidirectional"))
      (node (ref "R19") (pin "2") (pinfunction "2_2") (pintype "passive"))
    )
    (net (code "47") (name "Net-(QA5-C1)") (class "Default")
      (node (ref "QA5") (pin "3") (pinfunction "C1_3") (pintype "bidirectional"))
      (node (ref "U$1") (pin "C9") (pinfunction "C9_C9") (pintype "bidirectional"))
    )
    (net (code "48") (name "Net-(QA5-C2)") (class "Default")
      (node (ref "QA5") (pin "6") (pinfunction "C2_6") (pintype "bidirectional"))
      (node (ref "U$1") (pin "C10") (pinfunction "C10_C10") (pintype "bidirectional"))
    )
    (net (code "49") (name "Net-(QA6-B1)") (class "Default")
      (node (ref "QA6") (pin "5") (pinfunction "B1_5") (pintype "bidirectional"))
      (node (ref "R20") (pin "2") (pinfunction "2_2") (pintype "passive"))
    )
    (net (code "50") (name "Net-(QA6-B2)") (class "Default")
      (node (ref "QA6") (pin "2") (pinfunction "B2_2") (pintype "bidirectional"))
      (node (ref "R21") (pin "2") (pinfunction "2_2") (pintype "passive"))
    )
    (net (code "51") (name "Net-(QA6-C1)") (class "Default")
      (node (ref "QA6") (pin "3") (pinfunction "C1_3") (pintype "bidirectional"))
      (node (ref "U$1") (pin "C11") (pinfunction "C11_C11") (pintype "bidirectional"))
    )
    (net (code "52") (name "Net-(QA6-C2)") (class "Default")
      (node (ref "QA6") (pin "6") (pinfunction "C2_6") (pintype "bidirectional"))
      (node (ref "U$1") (pin "C12") (pinfunction "C12_C12") (pintype "bidirectional"))
    )
    (net (code "53") (name "Net-(QA7-B1)") (class "Default")
      (node (ref "QA7") (pin "5") (pinfunction "B1_5") (pintype "bidirectional"))
      (node (ref "R22") (pin "2") (pinfunction "2_2") (pintype "passive"))
    )
    (net (code "54") (name "Net-(QA7-B2)") (class "Default")
      (node (ref "QA7") (pin "2") (pinfunction "B2_2") (pintype "bidirectional"))
      (node (ref "R23") (pin "2") (pinfunction "2_2") (pintype "passive"))
    )
    (net (code "55") (name "Net-(QA7-C1)") (class "Default")
      (node (ref "QA7") (pin "3") (pinfunction "C1_3") (pintype "bidirectional"))
      (node (ref "U$1") (pin "C13") (pinfunction "C13_C13") (pintype "bidirectional"))
    )
    (net (code "56") (name "Net-(QA7-C2)") (class "Default")
      (node (ref "QA7") (pin "6") (pinfunction "C2_6") (pintype "bidirectional"))
      (node (ref "U$1") (pin "C14") (pinfunction "C14_C14") (pintype "bidirectional"))
    )
    (net (code "57") (name "Net-(QA8-B1)") (class "Default")
      (node (ref "QA8") (pin "5") (pinfunction "B1_5") (pintype "bidirectional"))
      (node (ref "R24") (pin "2") (pinfunction "2_2") (pintype "passive"))
    )
    (net (code "58") (name "Net-(QA8-B2)") (class "Default")
      (node (ref "QA8") (pin "2") (pinfunction "B2_2") (pintype "bidirectional"))
      (node (ref "R25") (pin "2") (pinfunction "2_2") (pintype "passive"))
    )
    (net (code "59") (name "Net-(QA8-C1)") (class "Default")
      (node (ref "QA8") (pin "3") (pinfunction "C1_3") (pintype "bidirectional"))
      (node (ref "U$1") (pin "C15") (pinfunction "C15_C15") (pintype "bidirectional"))
    )
    (net (code "60") (name "Net-(QA8-C2)") (class "Default")
      (node (ref "QA8") (pin "6") (pinfunction "C2_6") (pintype "bidirectional"))
      (node (ref "U$1") (pin "C16") (pinfunction "C16_C16") (pintype "bidirectional"))
    )
    (net (code "61") (name "Net-(QA9-B1)") (class "Default")
      (node (ref "QA9") (pin "5") (pinfunction "B1_5") (pintype "bidirectional"))
      (node (ref "R26") (pin "2") (pinfunction "2_2") (pintype "passive"))
    )
    (net (code "62") (name "Net-(QA9-B2)") (class "Default")
      (node (ref "QA9") (pin "2") (pinfunction "B2_2") (pintype "bidirectional"))
      (node (ref "R27") (pin "2") (pinfunction "2_2") (pintype "passive"))
    )
    (net (code "63") (name "Net-(QA9-C1)") (class "Default")
      (node (ref "QA9") (pin "3") (pinfunction "C1_3") (pintype "bidirectional"))
      (node (ref "U$1") (pin "C17") (pinfunction "C17_C17") (pintype "bidirectional"))
    )
    (net (code "64") (name "Net-(QA9-C2)") (class "Default")
      (node (ref "QA9") (pin "6") (pinfunction "C2_6") (pintype "bidirectional"))
      (node (ref "U$1") (pin "C18") (pinfunction "C18_C18") (pintype "bidirectional"))
    )
    (net (code "65") (name "Net-(QA10-B1)") (class "Default")
      (node (ref "QA10") (pin "5") (pinfunction "B1_5") (pintype "bidirectional"))
      (node (ref "R28") (pin "2") (pinfunction "2_2") (pintype "passive"))
    )
    (net (code "66") (name "Net-(QA10-B2)") (class "Default")
      (node (ref "QA10") (pin "2") (pinfunction "B2_2") (pintype "bidirectional"))
      (node (ref "R29") (pin "2") (pinfunction "2_2") (pintype "passive"))
    )
    (net (code "67") (name "Net-(QA10-C1)") (class "Default")
      (node (ref "QA10") (pin "3") (pinfunction "C1_3") (pintype "bidirectional"))
      (node (ref "U$1") (pin "C19") (pinfunction "C19_C19") (pintype "bidirectional"))
    )
    (net (code "68") (name "Net-(QA10-C2)") (class "Default")
      (node (ref "QA10") (pin "6") (pinfunction "C2_6") (pintype "bidirectional"))
      (node (ref "U$1") (pin "C20") (pinfunction "C20_C20") (pintype "bidirectional"))
    )
    (net (code "69") (name "Net-(QA11-B1)") (class "Default")
      (node (ref "QA11") (pin "5") (pinfunction "B1_5") (pintype "bidirectional"))
      (node (ref "R30") (pin "2") (pinfunction "2_2") (pintype "passive"))
    )
    (net (code "70") (name "Net-(QA11-B2)") (class "Default")
      (node (ref "QA11") (pin "2") (pinfunction "B2_2") (pintype "bidirectional"))
      (node (ref "R31") (pin "2") (pinfunction "2_2") (pintype "passive"))
    )
    (net (code "71") (name "Net-(QA11-C1)") (class "Default")
      (node (ref "QA11") (pin "3") (pinfunction "C1_3") (pintype "bidirectional"))
      (node (ref "U$1") (pin "C21") (pinfunction "C21_C21") (pintype "bidirectional"))
    )
    (net (code "72") (name "Net-(QA11-C2)") (class "Default")
      (node (ref "QA11") (pin "6") (pinfunction "C2_6") (pintype "bidirectional"))
      (node (ref "U$1") (pin "C22") (pinfunction "C22_C22") (pintype "bidirectional"))
    )
    (net (code "73") (name "Net-(QA12-B1)") (class "Default")
      (node (ref "QA12") (pin "5") (pinfunction "B1_5") (pintype "bidirectional"))
      (node (ref "R32") (pin "2") (pinfunction "2_2") (pintype "passive"))
    )
    (net (code "74") (name "Net-(QA12-B2)") (class "Default")
      (node (ref "QA12") (pin "2") (pinfunction "B2_2") (pintype "bidirectional"))
      (node (ref "R33") (pin "2") (pinfunction "2_2") (pintype "passive"))
    )
    (net (code "75") (name "Net-(QA12-C1)") (class "Default")
      (node (ref "QA12") (pin "3") (pinfunction "C1_3") (pintype "bidirectional"))
      (node (ref "U$1") (pin "C23") (pinfunction "C23_C23") (pintype "bidirectional"))
    )
    (net (code "76") (name "Net-(QA12-C2)") (class "Default")
      (node (ref "QA12") (pin "6") (pinfunction "C2_6") (pintype "bidirectional"))
      (node (ref "U$1") (pin "C24") (pinfunction "C24_C24") (pintype "bidirectional"))
    )
    (net (code "77") (name "Net-(R1-Pad2)") (class "Default")
      (node (ref "R1") (pin "2") (pinfunction "2_2") (pintype "passive"))
      (node (ref "U$1") (pin "A1@2") (pinfunction "A1_A1@2") (pintype "bidirectional"))
    )
    (net (code "78") (name "Net-(R2-Pad2)") (class "Default")
      (node (ref "R2") (pin "2") (pinfunction "2_2") (pintype "passive"))
      (node (ref "U$1") (pin "A2@2") (pinfunction "A2_A2@2") (pintype "bidirectional"))
    )
    (net (code "79") (name "Net-(R3-Pad2)") (class "Default")
      (node (ref "R3") (pin "2") (pinfunction "2_2") (pintype "passive"))
      (node (ref "U$1") (pin "A3@2") (pinfunction "A3_A3@2") (pintype "bidirectional"))
    )
    (net (code "80") (name "Net-(R5-Pad2)") (class "Default")
      (node (ref "R5") (pin "2") (pinfunction "2_2") (pintype "passive"))
      (node (ref "U$1") (pin "A4@2") (pinfunction "A4_A4@2") (pintype "bidirectional"))
    )
    (net (code "81") (name "Net-(R6-Pad2)") (class "Default")
      (node (ref "R6") (pin "2") (pinfunction "2_2") (pintype "passive"))
      (node (ref "U$1") (pin "A5@2") (pinfunction "A5_A5@2") (pintype "bidirectional"))
    )
    (net (code "82") (name "Net-(R7-Pad2)") (class "Default")
      (node (ref "R7") (pin "2") (pinfunction "2_2") (pintype "passive"))
      (node (ref "U$1") (pin "A6@2") (pinfunction "A6_A6@2") (pintype "bidirectional"))
    )
    (net (code "83") (name "Net-(R8-Pad2)") (class "Default")
      (node (ref "R8") (pin "2") (pinfunction "2_2") (pintype "passive"))
      (node (ref "U$1") (pin "A7@2") (pinfunction "A7_A7@2") (pintype "bidirectional"))
    )
    (net (code "84") (name "Net-(U1-RA2)") (class "Default")
      (node (ref "Q1") (pin "E") (pinfunction "E_E") (pintype "passive"))
      (node (ref "R9") (pin "2") (pinfunction "2_2") (pintype "passive"))
      (node (ref "U1") (pin "1") (pinfunction "RA2_1") (pintype "bidirectional"))
    )
    (net (code "85") (name "Net-(U2-CP0)") (class "Default")
      (node (ref "U2") (pin "14") (pinfunction "CP0_14") (pintype "bidirectional"))
      (node (ref "U6") (pin "4") (pinfunction "O_4") (pintype "output"))
    )
    (net (code "86") (name "Net-(U2-MR)") (class "Default")
      (node (ref "U2") (pin "15") (pinfunction "MR_15") (pintype "bidirectional"))
      (node (ref "U3") (pin "3") (pinfunction "Q0_3") (pintype "bidirectional"))
    )
    (net (code "87") (name "Net-(U3-CP0)") (class "Default")
      (node (ref "U3") (pin "14") (pinfunction "CP0_14") (pintype "bidirectional"))
      (node (ref "U5") (pin "4") (pinfunction "O_4") (pintype "output"))
    )
    (net (code "88") (name "Net-(U3-MR)") (class "Default")
      (node (ref "U3") (pin "15") (pinfunction "MR_15") (pintype "bidirectional"))
      (node (ref "U4") (pin "3") (pinfunction "Q0_3") (pintype "bidirectional"))
    )
    (net (code "89") (name "Net-(U3-Q9)") (class "Default")
      (node (ref "U3") (pin "11") (pinfunction "Q9_11") (pintype "bidirectional"))
      (node (ref "U3") (pin "13") (pinfunction "~{CP1}_13") (pintype "bidirectional"))
      (node (ref "U6") (pin "1") (pinfunction "I0_1") (pintype "input"))
    )
    (net (code "90") (name "Net-(U4-Q9)") (class "Default")
      (node (ref "U4") (pin "11") (pinfunction "Q9_11") (pintype "bidirectional"))
      (node (ref "U4") (pin "13") (pinfunction "~{CP1}_13") (pintype "bidirectional"))
      (node (ref "U5") (pin "1") (pinfunction "I0_1") (pintype "input"))
    )
    (net (code "91") (name "PGD") (class "Default")
      (node (ref "J1") (pin "6") (pinfunction "S_6") (pintype "bidirectional"))
      (node (ref "U1") (pin "14") (pinfunction "RB7_14") (pintype "bidirectional"))
    )
    (net (code "92") (name "ROW1") (class "Default")
      (node (ref "R1") (pin "1") (pinfunction "1_1") (pintype "passive"))
      (node (ref "U1") (pin "7") (pinfunction "RB0/INT_7") (pintype "bidirectional"))
    )
    (net (code "93") (name "ROW2") (class "Default")
      (node (ref "R2") (pin "1") (pinfunction "1_1") (pintype "passive"))
      (node (ref "U1") (pin "8") (pinfunction "RB1_8") (pintype "bidirectional"))
    )
    (net (code "94") (name "ROW3") (class "Default")
      (node (ref "R3") (pin "1") (pinfunction "1_1") (pintype "passive"))
      (node (ref "U1") (pin "9") (pinfunction "RB2_9") (pintype "bidirectional"))
    )
    (net (code "95") (name "ROW4") (class "Default")
      (node (ref "R5") (pin "1") (pinfunction "1_1") (pintype "passive"))
      (node (ref "U1") (pin "10") (pinfunction "RB3_10") (pintype "bidirectional"))
    )
    (net (code "96") (name "ROW5") (class "Default")
      (node (ref "R6") (pin "1") (pinfunction "1_1") (pintype "passive"))
      (node (ref "U1") (pin "11") (pinfunction "RB4_11") (pintype "bidirectional"))
    )
    (net (code "97") (name "ROW6") (class "Default")
      (node (ref "R7") (pin "1") (pinfunction "1_1") (pintype "passive"))
      (node (ref "U1") (pin "12") (pinfunction "RB5_12") (pintype "bidirectional"))
    )
    (net (code "98") (name "ROW7{slash}PGC") (class "Default")
      (node (ref "J1") (pin "5") (pinfunction "S_5") (pintype "bidirectional"))
      (node (ref "R8") (pin "1") (pinfunction "1_1") (pintype "passive"))
      (node (ref "U1") (pin "13") (pinfunction "RB6_13") (pintype "bidirectional"))
    )
    (net (code "99") (name "SCL") (class "Default")
      (node (ref "J1") (pin "3") (pinfunction "S_3") (pintype "bidirectional"))
      (node (ref "U1") (pin "17") (pinfunction "RA6/OSC2_17") (pintype "bidirectional"))
    )
    (net (code "100") (name "SDA") (class "Default")
      (node (ref "J1") (pin "2") (pinfunction "S_2") (pintype "bidirectional"))
      (node (ref "U1") (pin "18") (pinfunction "RA7/OSC1_18") (pintype "bidirectional"))
    )
    (net (code "101") (name "VPP{slash}~{MCLR}") (class "Default")
      (node (ref "J1") (pin "7") (pinfunction "S_7") (pintype "bidirectional"))
      (node (ref "U1") (pin "4") (pinfunction "RA5/~{MCLR}/VPP_4") (pintype "bidirectional"))
    )
    (net (code "102") (name "unconnected-(U$1-A1-PadA1@1)") (class "Default")
      (node (ref "U$1") (pin "A1@1") (pinfunction "A1_A1@1") (pintype "bidirectional"))
    )
    (net (code "103") (name "unconnected-(U$1-A2-PadA2@1)") (class "Default")
      (node (ref "U$1") (pin "A2@1") (pinfunction "A2_A2@1") (pintype "bidirectional"))
    )
    (net (code "104") (name "unconnected-(U$1-A3-PadA3@1)") (class "Default")
      (node (ref "U$1") (pin "A3@1") (pinfunction "A3_A3@1") (pintype "bidirectional"))
    )
    (net (code "105") (name "unconnected-(U$1-A4-PadA4@1)") (class "Default")
      (node (ref "U$1") (pin "A4@1") (pinfunction "A4_A4@1") (pintype "bidirectional"))
    )
    (net (code "106") (name "unconnected-(U$1-A5-PadA5@1)") (class "Default")
      (node (ref "U$1") (pin "A5@1") (pinfunction "A5_A5@1") (pintype "bidirectional"))
    )
    (net (code "107") (name "unconnected-(U$1-A6-PadA6@1)") (class "Default")
      (node (ref "U$1") (pin "A6@1") (pinfunction "A6_A6@1") (pintype "bidirectional"))
    )
    (net (code "108") (name "unconnected-(U$1-A7-PadA7@1)") (class "Default")
      (node (ref "U$1") (pin "A7@1") (pinfunction "A7_A7@1") (pintype "bidirectional"))
    )
    (net (code "109") (name "unconnected-(U1-RA3-Pad2)") (class "Default")
      (node (ref "U1") (pin "2") (pinfunction "RA3_2") (pintype "bidirectional"))
    )
    (net (code "110") (name "unconnected-(U1-RA4-Pad3)") (class "Default")
      (node (ref "U1") (pin "3") (pinfunction "RA4_3") (pintype "bidirectional"))
    )
    (net (code "111") (name "unconnected-(U2-Q0-Pad3)") (class "Default")
      (node (ref "U2") (pin "3") (pinfunction "Q0_3") (pintype "bidirectional"))
    )
    (net (code "112") (name "unconnected-(U2-Q9-Pad11)") (class "Default")
      (node (ref "U2") (pin "11") (pinfunction "Q9_11") (pintype "bidirectional"))
    )
    (net (code "113") (name "unconnected-(U2-~{Q}5-9-Pad12)") (class "Default")
      (node (ref "U2") (pin "12") (pinfunction "~{Q}5-9_12") (pintype "bidirectional"))
    )
    (net (code "114") (name "unconnected-(U3-~{Q}5-9-Pad12)") (class "Default")
      (node (ref "U3") (pin "12") (pinfunction "~{Q}5-9_12") (pintype "bidirectional"))
    )
    (net (code "115") (name "unconnected-(U4-~{Q}5-9-Pad12)") (class "Default")
      (node (ref "U4") (pin "12") (pinfunction "~{Q}5-9_12") (pintype "bidirectional"))
    )
  )
)
